# EMG_V2.net
KiCad netlist of a schematic drawn in Altium Designer
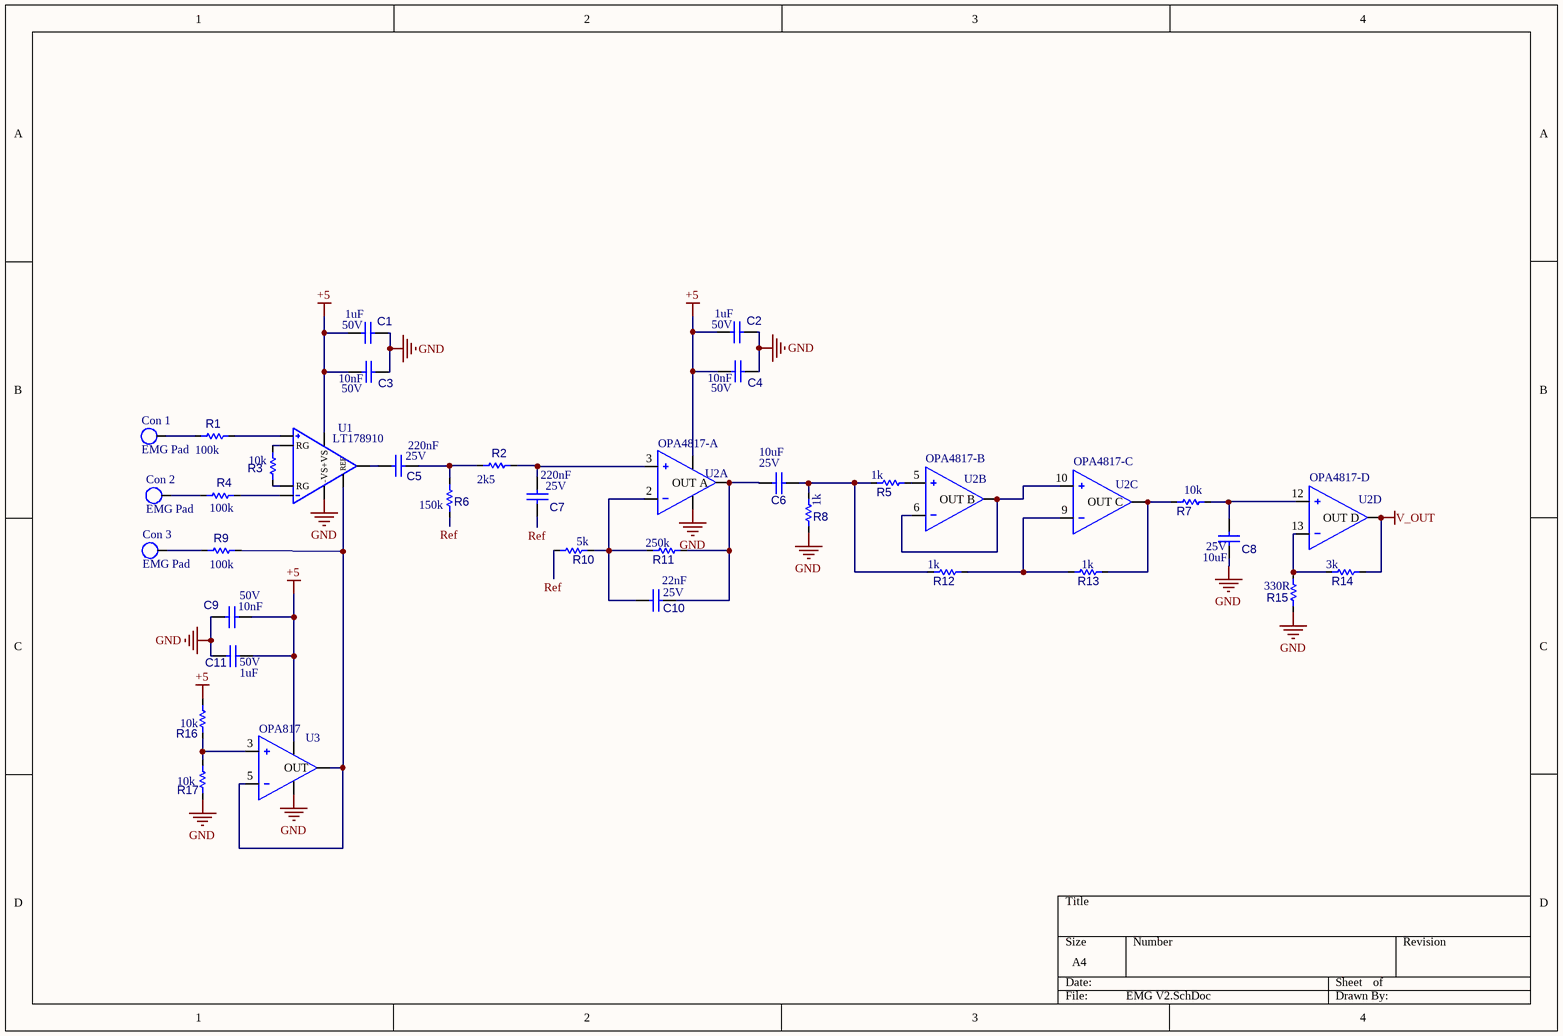
[diagram p0: EMG V2.SchDoc]

(export (version "E")
  (design (tool "Eeschema 10.0.6"))
  (components
    (comp (ref "C1")
      (value "1uF")
      (footprint "0603_Cap:0603 Capacitor")
      (description "1uF/50V")
      (fields
        (field (name "TOLERANCE") "20%")
        (field (name "MANUFACTURER") "Any")
        (field (name "VOLTAGE") "50V")
      )
      (libsource (lib "1uF 50V 0603") (part "1uF/50V"))
    )
    (comp (ref "C2")
      (value "1uF")
      (footprint "0603_Cap:0603 Capacitor")
      (description "1uF/50V")
      (fields
        (field (name "TOLERANCE") "20%")
        (field (name "MANUFACTURER") "Any")
        (field (name "VOLTAGE") "50V")
      )
      (libsource (lib "1uF 50V 0603") (part "1uF/50V"))
    )
    (comp (ref "C3")
      (value "10nF")
      (footprint "0603_Cap:0603 Capacitor")
      (description "10nF/50V")
      (fields
        (field (name "TOLERANCE") "20%")
        (field (name "MANUFACTURER") "Any")
        (field (name "VOLTAGE") "50V")
      )
      (libsource (lib "10nF 50V 0603") (part "10nF/50V"))
    )
    (comp (ref "C4")
      (value "10nF")
      (footprint "0603_Cap:0603 Capacitor")
      (description "10nF/50V")
      (fields
        (field (name "TOLERANCE") "20%")
        (field (name "MANUFACTURER") "Any")
        (field (name "VOLTAGE") "50V")
      )
      (libsource (lib "10nF 50V 0603") (part "10nF/50V"))
    )
    (comp (ref "C5")
      (value "220nF")
      (footprint "0603 Capacitor")
      (description "220nF/25V")
      (fields
        (field (name "TOLERANCE") "20%")
        (field (name "MANUFACTURER") "Any")
        (field (name "VOLTAGE") "25V")
      )
      (libsource (lib "220nF 25V 0603") (part "220nF/25V"))
    )
    (comp (ref "C6")
      (value "10uF")
      (footprint "0603_Cap:0603 Capacitor")
      (description "10uF/25V")
      (fields
        (field (name "TOLERANCE") "20%")
        (field (name "MANUFACTURER") "Any")
        (field (name "VOLTAGE") "25V")
      )
      (libsource (lib "10uF 25V 0603") (part "10uF/25V"))
    )
    (comp (ref "C7")
      (value "220nF")
      (footprint "0603 Capacitor")
      (description "220nF/25V")
      (fields
        (field (name "TOLERANCE") "20%")
        (field (name "MANUFACTURER") "Any")
        (field (name "VOLTAGE") "25V")
      )
      (libsource (lib "220nF 25V 0603") (part "220nF/25V"))
    )
    (comp (ref "C8")
      (value "10uF")
      (footprint "0603_Cap:0603 Capacitor")
      (description "10uF/25V")
      (fields
        (field (name "TOLERANCE") "20%")
        (field (name "MANUFACTURER") "Any")
        (field (name "VOLTAGE") "25V")
      )
      (libsource (lib "10uF 25V 0603") (part "10uF/25V"))
    )
    (comp (ref "C9")
      (value "10nF")
      (footprint "0603_Cap:0603 Capacitor")
      (description "10nF/50V")
      (fields
        (field (name "TOLERANCE") "20%")
        (field (name "MANUFACTURER") "Any")
        (field (name "VOLTAGE") "50V")
      )
      (libsource (lib "10nF 50V 0603") (part "10nF/50V"))
    )
    (comp (ref "C10")
      (value "22nF")
      (footprint "0603_Cap:0603 Capacitor")
      (description "22nF/25V")
      (fields
        (field (name "TOLERANCE") "20%")
        (field (name "MANUFACTURER") "Any")
        (field (name "VOLTAGE") "25V")
      )
      (libsource (lib "22nF 25V 0603") (part "22nF/25V"))
    )
    (comp (ref "C11")
      (value "1uF")
      (footprint "0603_Cap:0603 Capacitor")
      (description "1uF/50V")
      (fields
        (field (name "TOLERANCE") "20%")
        (field (name "MANUFACTURER") "Any")
        (field (name "VOLTAGE") "50V")
      )
      (libsource (lib "1uF 50V 0603") (part "1uF/50V"))
    )
    (comp (ref "Con 1")
      (value "EMG Pad")
      (footprint "EMG Pad:PCBComponent_1")
      (libsource (lib "EMG Pad") (part "Pad"))
    )
    (comp (ref "Con 2")
      (value "EMG Pad")
      (footprint "EMG Pad:PCBComponent_1")
      (libsource (lib "EMG Pad") (part "Pad"))
    )
    (comp (ref "Con 3")
      (value "EMG Pad")
      (footprint "EMG Pad:PCBComponent_1")
      (libsource (lib "EMG Pad") (part "Pad"))
    )
    (comp (ref "R1")
      (value "100k")
      (footprint "0603_Res:0603 Resistor")
      (fields
        (field (name "TOLERANCE") "10%")
        (field (name "MANUFACTURER") "Any")
        (field (name "150K") "100k")
      )
      (libsource (lib "100K 0603") (part "100k"))
    )
    (comp (ref "R2")
      (value "2k5")
      (footprint "0603_Res:0603 Resistor")
      (fields (field (name "TOLERANCE") "10%") (field (name "MANUFACTURER") "Any"))
      (libsource (lib "2K5 0603") (part "2k5"))
    )
    (comp (ref "R3")
      (value "10k")
      (footprint "0603_Res:0603 Resistor")
      (fields (field (name "TOLERANCE") "10%") (field (name "MANUFACTURER") "Any"))
      (libsource (lib "10k 0603") (part "10k"))
    )
    (comp (ref "R4")
      (value "100k")
      (footprint "0603_Res:0603 Resistor")
      (fields
        (field (name "TOLERANCE") "10%")
        (field (name "MANUFACTURER") "Any")
        (field (name "150K") "100k")
      )
      (libsource (lib "100K 0603") (part "100k"))
    )
    (comp (ref "R5")
      (value "1k")
      (footprint "0603 Resistor")
      (fields (field (name "TOLERANCE") "10%") (field (name "MANUFACTURER") "Any"))
      (libsource (lib "1K 0603") (part "1k"))
    )
    (comp (ref "R6")
      (value "150k")
      (footprint "0603_Res:0603 Resistor")
      (fields
        (field (name "TOLERANCE") "10%")
        (field (name "MANUFACTURER") "Any")
        (field (name "150K") "150k")
      )
      (libsource (lib "150K 0603") (part "150k"))
    )
    (comp (ref "R7")
      (value "10k")
      (footprint "0603 Resistor")
      (fields (field (name "TOLERANCE") "10%") (field (name "MANUFACTURER") "Any"))
      (libsource (lib "10k 0603") (part "10k"))
    )
    (comp (ref "R8")
      (value "1k")
      (footprint "0603 Resistor")
      (fields (field (name "TOLERANCE") "10%") (field (name "MANUFACTURER") "Any"))
      (libsource (lib "1K 0603") (part "1k"))
    )
    (comp (ref "R9")
      (value "100k")
      (footprint "0603_Res:0603 Resistor")
      (fields
        (field (name "TOLERANCE") "10%")
        (field (name "MANUFACTURER") "Any")
        (field (name "150K") "100k")
      )
      (libsource (lib "100K 0603") (part "100k"))
    )
    (comp (ref "R10")
      (value "5k")
      (footprint "0603 Resistor")
      (fields (field (name "TOLERANCE") "10%") (field (name "MANUFACTURER") "Any"))
      (libsource (lib "5K 0603") (part "5k"))
    )
    (comp (ref "R11")
      (value "250k")
      (footprint "0603 Resistor")
      (fields (field (name "TOLERANCE") "10%") (field (name "MANUFACTURER") "Any"))
      (libsource (lib "250K 0603") (part "250k"))
    )
    (comp (ref "R12")
      (value "1k")
      (footprint "0603 Resistor")
      (fields (field (name "TOLERANCE") "10%") (field (name "MANUFACTURER") "Any"))
      (libsource (lib "1K 0603") (part "1k"))
    )
    (comp (ref "R13")
      (value "1k")
      (footprint "0603 Resistor")
      (fields (field (name "TOLERANCE") "10%") (field (name "MANUFACTURER") "Any"))
      (libsource (lib "1K 0603") (part "1k"))
    )
    (comp (ref "R14")
      (value "3k")
      (footprint "0603 Resistor")
      (fields (field (name "TOLERANCE") "10%") (field (name "MANUFACTURER") "Any"))
      (libsource (lib "3K 0603") (part "3k"))
    )
    (comp (ref "R15")
      (value "330R")
      (footprint "0603 Resistor")
      (fields (field (name "TOLERANCE") "10%") (field (name "MANUFACTURER") "Any"))
      (libsource (lib "330 R 0603") (part "330R"))
    )
    (comp (ref "R16")
      (value "10k")
      (footprint "0603 Resistor")
      (fields (field (name "TOLERANCE") "10%") (field (name "MANUFACTURER") "Any"))
      (libsource (lib "10k 0603") (part "10k"))
    )
    (comp (ref "R17")
      (value "10k")
      (footprint "0603 Resistor")
      (fields (field (name "TOLERANCE") "10%") (field (name "MANUFACTURER") "Any"))
      (libsource (lib "10k 0603") (part "10k"))
    )
    (comp (ref "U1")
      (value "LT178910")
      (footprint "SOIC 8 LT178910")
      (description "Micropower, Single Supply Rail-to-Rail, Output Instrumentation Amplifiers")
      (fields (field (name "MANUFACTURER") "Linear Technologiy"))
      (libsource (lib "EMG Integrated Library") (part "LT178910-2"))
    )
    (comp (ref "U2")
      (value "OPA4817")
      (footprint "TSSOP14 OPA4187")
      (description "OPAx187, Low Power, Rail-to-Rail Output,36-V Operational Amplifiers")
      (fields (field (name "MANUFACTURER") "TEXAS INSTRUMENTS"))
      (libsource (lib "EMG Integrated Library") (part "OPA4817-2"))
    )
    (comp (ref "U3")
      (value "OPA187")
      (footprint "SOT23-5")
      (description "OPAx187, Low Power, Rail-to-Rail Output,36-V Operational Amplifiers")
      (fields (field (name "MANUFACTURER") "TEXAS INSTRUMENTS"))
      (libsource (lib "EMG Integrated Library") (part "OPA187-2"))
    )
  )
  (nets
    (net (code "1") (name "+5") (class "Default")
      (node (ref "C1") (pin "1") (pinfunction "1_1") (pintype "passive"))
      (node (ref "C11") (pin "1") (pinfunction "1_1") (pintype "passive"))
      (node (ref "C2") (pin "1") (pinfunction "1_1") (pintype "passive"))
      (node (ref "C3") (pin "1") (pinfunction "1_1") (pintype "passive"))
      (node (ref "C4") (pin "1") (pinfunction "1_1") (pintype "passive"))
      (node (ref "C9") (pin "1") (pinfunction "1_1") (pintype "passive"))
      (node (ref "R16") (pin "1") (pinfunction "1_1") (pintype "passive"))
      (node (ref "U1") (pin "7") (pinfunction "+VS_7") (pintype "power_in"))
      (node (ref "U2") (pin "4") (pinfunction "V+_4") (pintype "power_in"))
      (node (ref "U3") (pin "4") (pinfunction "V+_4") (pintype "power_in"))
    )
    (net (code "2") (name "/Ref") (class "Default")
      (node (ref "C7") (pin "2") (pinfunction "2_2") (pintype "passive"))
      (node (ref "R10") (pin "1") (pinfunction "1_1") (pintype "passive"))
      (node (ref "R6") (pin "2") (pinfunction "2_2") (pintype "passive"))
    )
    (net (code "3") (name "GND") (class "Default")
      (node (ref "C1") (pin "2") (pinfunction "2_2") (pintype "passive"))
      (node (ref "C11") (pin "2") (pinfunction "2_2") (pintype "passive"))
      (node (ref "C2") (pin "2") (pinfunction "2_2") (pintype "passive"))
      (node (ref "C3") (pin "2") (pinfunction "2_2") (pintype "passive"))
      (node (ref "C4") (pin "2") (pinfunction "2_2") (pintype "passive"))
      (node (ref "C8") (pin "2") (pinfunction "2_2") (pintype "passive"))
      (node (ref "C9") (pin "2") (pinfunction "2_2") (pintype "passive"))
      (node (ref "R15") (pin "2") (pinfunction "2_2") (pintype "passive"))
      (node (ref "R17") (pin "2") (pinfunction "2_2") (pintype "passive"))
      (node (ref "R8") (pin "2") (pinfunction "2_2") (pintype "passive"))
      (node (ref "U1") (pin "4") (pinfunction "-VS_4") (pintype "power_in"))
      (node (ref "U2") (pin "11") (pinfunction "V-_11") (pintype "passive"))
      (node (ref "U3") (pin "2") (pinfunction "V-_2") (pintype "passive"))
    )
    (net (code "4") (name "Net-(C5-Pad2)") (class "Default")
      (node (ref "C5") (pin "2") (pinfunction "2_2") (pintype "passive"))
      (node (ref "R2") (pin "1") (pinfunction "1_1") (pintype "passive"))
      (node (ref "R6") (pin "1") (pinfunction "1_1") (pintype "passive"))
    )
    (net (code "5") (name "Net-(C6-Pad2)") (class "Default")
      (node (ref "C6") (pin "2") (pinfunction "2_2") (pintype "passive"))
      (node (ref "R12") (pin "1") (pinfunction "1_1") (pintype "passive"))
      (node (ref "R5") (pin "1") (pinfunction "1_1") (pintype "passive"))
      (node (ref "R8") (pin "1") (pinfunction "1_1") (pintype "passive"))
    )
    (net (code "6") (name "Net-(Con 1-Pad1)") (class "Default")
      (node (ref "Con 1") (pin "1") (pinfunction "1_1") (pintype "passive"))
      (node (ref "R1") (pin "1") (pinfunction "1_1") (pintype "passive"))
    )
    (net (code "7") (name "Net-(Con 2-Pad1)") (class "Default")
      (node (ref "Con 2") (pin "1") (pinfunction "1_1") (pintype "passive"))
      (node (ref "R4") (pin "1") (pinfunction "1_1") (pintype "passive"))
    )
    (net (code "8") (name "Net-(Con 3-Pad1)") (class "Default")
      (node (ref "Con 3") (pin "1") (pinfunction "1_1") (pintype "passive"))
      (node (ref "R9") (pin "1") (pinfunction "1_1") (pintype "passive"))
    )
    (net (code "9") (name "Net-(R3-Pad1)") (class "Default")
      (node (ref "R3") (pin "1") (pinfunction "1_1") (pintype "passive"))
      (node (ref "U1") (pin "1") (pinfunction "RG_1") (pintype "passive"))
    )
    (net (code "10") (name "Net-(R3-Pad2)") (class "Default")
      (node (ref "R3") (pin "2") (pinfunction "2_2") (pintype "passive"))
      (node (ref "U1") (pin "8") (pinfunction "RG_8") (pintype "passive"))
    )
    (net (code "11") (name "Net-(U1-+IN)") (class "Default")
      (node (ref "R1") (pin "2") (pinfunction "2_2") (pintype "passive"))
      (node (ref "U1") (pin "3") (pinfunction "+IN_3") (pintype "passive"))
    )
    (net (code "12") (name "Net-(U1--IN)") (class "Default")
      (node (ref "R4") (pin "2") (pinfunction "2_2") (pintype "passive"))
      (node (ref "U1") (pin "2") (pinfunction "-IN_2") (pintype "passive"))
    )
    (net (code "13") (name "Net-(U1-OUT)") (class "Default")
      (node (ref "C5") (pin "1") (pinfunction "1_1") (pintype "passive"))
      (node (ref "U1") (pin "6") (pinfunction "OUT_6") (pintype "passive"))
    )
    (net (code "14") (name "Net-(U1-REF)") (class "Default")
      (node (ref "R9") (pin "2") (pinfunction "2_2") (pintype "passive"))
      (node (ref "U1") (pin "5") (pinfunction "REF_5") (pintype "passive"))
      (node (ref "U3") (pin "1") (pinfunction "OUT_1") (pintype "passive"))
      (node (ref "U3") (pin "5") (pinfunction "-IN_5") (pintype "passive"))
    )
    (net (code "15") (name "Net-(U2A-+IN_A)") (class "Default")
      (node (ref "C7") (pin "1") (pinfunction "1_1") (pintype "passive"))
      (node (ref "R2") (pin "2") (pinfunction "2_2") (pintype "passive"))
      (node (ref "U2") (pin "3") (pinfunction "+IN_A_3") (pintype "passive"))
    )
    (net (code "16") (name "Net-(U2A--IN_A)") (class "Default")
      (node (ref "C10") (pin "1") (pinfunction "1_1") (pintype "passive"))
      (node (ref "R10") (pin "2") (pinfunction "2_2") (pintype "passive"))
      (node (ref "R11") (pin "1") (pinfunction "1_1") (pintype "passive"))
      (node (ref "U2") (pin "2") (pinfunction "-IN_A_2") (pintype "passive"))
    )
    (net (code "17") (name "Net-(U2A-OUT_A)") (class "Default")
      (node (ref "C10") (pin "2") (pinfunction "2_2") (pintype "passive"))
      (node (ref "C6") (pin "1") (pinfunction "1_1") (pintype "passive"))
      (node (ref "R11") (pin "2") (pinfunction "2_2") (pintype "passive"))
      (node (ref "U2") (pin "1") (pinfunction "OUT_A_1") (pintype "passive"))
    )
    (net (code "18") (name "Net-(U2B-+IN_B)") (class "Default")
      (node (ref "R5") (pin "2") (pinfunction "2_2") (pintype "passive"))
      (node (ref "U2") (pin "5") (pinfunction "+IN_B_5") (pintype "passive"))
    )
    (net (code "19") (name "Net-(U2B--IN_B)") (class "Default")
      (node (ref "U2") (pin "10") (pinfunction "+IN_C_10") (pintype "passive"))
      (node (ref "U2") (pin "6") (pinfunction "-IN_B_6") (pintype "passive"))
      (node (ref "U2") (pin "7") (pinfunction "OUT_B_7") (pintype "passive"))
    )
    (net (code "20") (name "Net-(U2C--IN_C)") (class "Default")
      (node (ref "R12") (pin "2") (pinfunction "2_2") (pintype "passive"))
      (node (ref "R13") (pin "1") (pinfunction "1_1") (pintype "passive"))
      (node (ref "U2") (pin "9") (pinfunction "-IN_C_9") (pintype "passive"))
    )
    (net (code "21") (name "Net-(U2C-OUT_C)") (class "Default")
      (node (ref "R13") (pin "2") (pinfunction "2_2") (pintype "passive"))
      (node (ref "R7") (pin "1") (pinfunction "1_1") (pintype "passive"))
      (node (ref "U2") (pin "8") (pinfunction "OUT_C_8") (pintype "passive"))
    )
    (net (code "22") (name "Net-(U2D-+IN_C)") (class "Default")
      (node (ref "C8") (pin "1") (pinfunction "1_1") (pintype "passive"))
      (node (ref "R7") (pin "2") (pinfunction "2_2") (pintype "passive"))
      (node (ref "U2") (pin "12") (pinfunction "+IN_C_12") (pintype "passive"))
    )
    (net (code "23") (name "Net-(U2D--IN_C)") (class "Default")
      (node (ref "R14") (pin "1") (pinfunction "1_1") (pintype "passive"))
      (node (ref "R15") (pin "1") (pinfunction "1_1") (pintype "passive"))
      (node (ref "U2") (pin "13") (pinfunction "-IN_C_13") (pintype "passive"))
    )
    (net (code "24") (name "Net-(U3-+IN)") (class "Default")
      (node (ref "R16") (pin "2") (pinfunction "2_2") (pintype "passive"))
      (node (ref "R17") (pin "1") (pinfunction "1_1") (pintype "passive"))
      (node (ref "U3") (pin "3") (pinfunction "+IN_3") (pintype "passive"))
    )
    (net (code "25") (name "V_OUT") (class "Default")
      (node (ref "R14") (pin "2") (pinfunction "2_2") (pintype "passive"))
      (node (ref "U2") (pin "14") (pinfunction "OUT_D_14") (pintype "passive"))
    )
  )
)
